# STM32F446RC_single_layer_V2_labelled.net
KiCad netlist of a schematic drawn in EAGLE
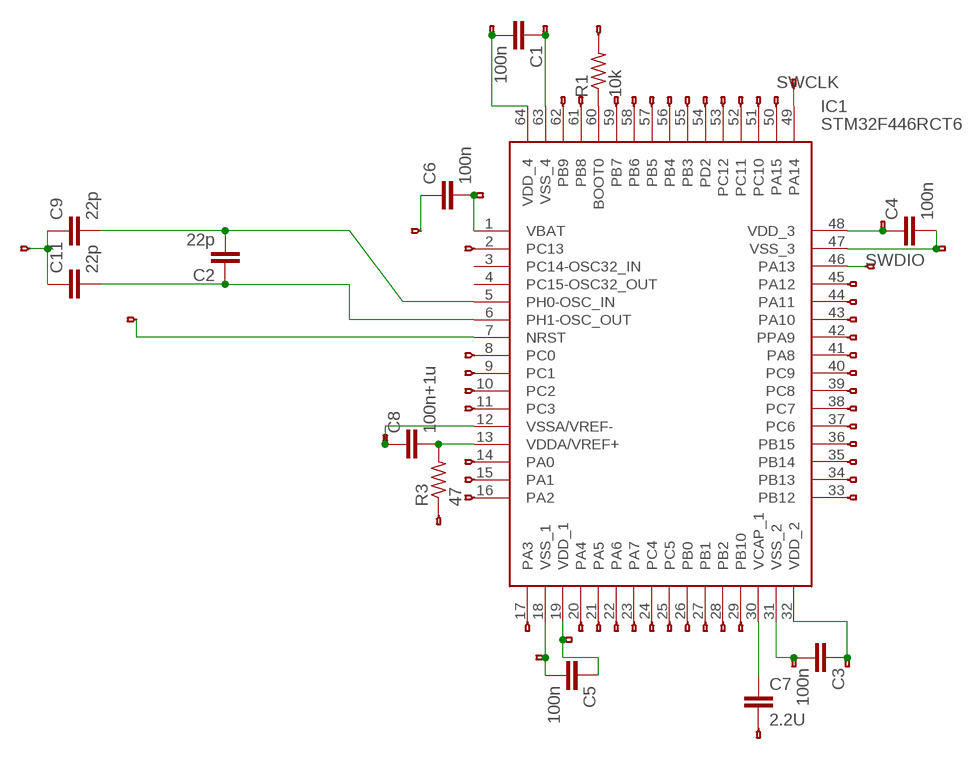
[diagram p0: schematic, sheet 1]

(export (version "E")
  (design (tool "Eeschema 10.0.6"))
  (components
    (comp (ref "C1")
      (value "100n")
      (footprint "eagle-import:C2.5-3")
      (libsource (lib "eagle-import") (part "C2,5-3"))
    )
    (comp (ref "C2")
      (value "22p")
      (footprint "eagle-import:C2.5-3")
      (libsource (lib "eagle-import") (part "C2,5-3"))
    )
    (comp (ref "C3")
      (value "100n")
      (footprint "eagle-import:C2.5-3")
      (libsource (lib "eagle-import") (part "C2,5-3"))
    )
    (comp (ref "C4")
      (value "100n")
      (footprint "eagle-import:C2.5-3")
      (libsource (lib "eagle-import") (part "C2,5-3"))
    )
    (comp (ref "C5")
      (value "100n")
      (footprint "eagle-import:C2.5-3")
      (libsource (lib "eagle-import") (part "C2,5-3"))
    )
    (comp (ref "C6")
      (value "100n")
      (footprint "eagle-import:C2.5-3")
      (libsource (lib "eagle-import") (part "C2,5-3"))
    )
    (comp (ref "C7")
      (value "2.2U")
      (footprint "eagle-import:C2.5-3")
      (libsource (lib "eagle-import") (part "C2,5-3"))
    )
    (comp (ref "C8")
      (value "100n+1u")
      (footprint "eagle-import:C2.5-3")
      (libsource (lib "eagle-import") (part "C2,5-3"))
    )
    (comp (ref "C9")
      (value "22p")
      (footprint "eagle-import:C2.5-3")
      (libsource (lib "eagle-import") (part "C2,5-3"))
    )
    (comp (ref "C11")
      (value "22p")
      (footprint "eagle-import:C2.5-3")
      (libsource (lib "eagle-import") (part "C2,5-3"))
    )
    (comp (ref "IC1")
      (value "STM32F446RCT6")
      (footprint "eagle-import:QFP50P1200X1200X160-64N")
      (fields (field (name "MOUSER_PART_NUMBER") "511-STM32F446RCT6"))
      (libsource (lib "eagle-import") (part "STM32F446RCT6"))
    )
    (comp (ref "JP1")
      (value "HEADERHOLE-HEADERHOLE")
      (footprint "eagle-import:1X1-HEADER-HOLE")
      (libsource (lib "eagle-import") (part "HEADERHOLE-HEADERHOLE"))
    )
    (comp (ref "JP2")
      (value "HEADERHOLE-HEADERHOLE")
      (footprint "eagle-import:1X1-HEADER-HOLE")
      (libsource (lib "eagle-import") (part "HEADERHOLE-HEADERHOLE"))
    )
    (comp (ref "JP3")
      (value "HEADERHOLE-HEADERHOLE")
      (footprint "eagle-import:1X1-HEADER-HOLE")
      (libsource (lib "eagle-import") (part "HEADERHOLE-HEADERHOLE"))
    )
    (comp (ref "JP4")
      (value "HEADERHOLE-HEADERHOLE")
      (footprint "eagle-import:1X1-HEADER-HOLE")
      (libsource (lib "eagle-import") (part "HEADERHOLE-HEADERHOLE"))
    )
    (comp (ref "JP5")
      (value "HEADERHOLE-HEADERHOLE")
      (footprint "eagle-import:1X1-HEADER-HOLE")
      (libsource (lib "eagle-import") (part "HEADERHOLE-HEADERHOLE"))
    )
    (comp (ref "JP6")
      (value "HEADERHOLE-HEADERHOLE")
      (footprint "eagle-import:1X1-HEADER-HOLE")
      (libsource (lib "eagle-import") (part "HEADERHOLE-HEADERHOLE"))
    )
    (comp (ref "JP7")
      (value "HEADERHOLE-HEADERHOLE")
      (footprint "eagle-import:1X1-HEADER-HOLE")
      (libsource (lib "eagle-import") (part "HEADERHOLE-HEADERHOLE"))
    )
    (comp (ref "JP9")
      (value "HEADERHOLE-HEADERHOLE")
      (footprint "eagle-import:1X1-HEADER-HOLE")
      (libsource (lib "eagle-import") (part "HEADERHOLE-HEADERHOLE"))
    )
    (comp (ref "JP10")
      (value "HEADERHOLE-HEADERHOLE")
      (footprint "eagle-import:1X1-HEADER-HOLE")
      (libsource (lib "eagle-import") (part "HEADERHOLE-HEADERHOLE"))
    )
    (comp (ref "JP11")
      (value "HEADERHOLE-HEADERHOLE")
      (footprint "eagle-import:1X1-HEADER-HOLE")
      (libsource (lib "eagle-import") (part "HEADERHOLE-HEADERHOLE"))
    )
    (comp (ref "JP12")
      (value "HEADERHOLE-HEADERHOLE")
      (footprint "eagle-import:1X1-HEADER-HOLE")
      (libsource (lib "eagle-import") (part "HEADERHOLE-HEADERHOLE"))
    )
    (comp (ref "JP13")
      (value "HEADERHOLE-HEADERHOLE")
      (footprint "eagle-import:1X1-HEADER-HOLE")
      (libsource (lib "eagle-import") (part "HEADERHOLE-HEADERHOLE"))
    )
    (comp (ref "JP14")
      (value "HEADERHOLE-HEADERHOLE")
      (footprint "eagle-import:1X1-HEADER-HOLE")
      (libsource (lib "eagle-import") (part "HEADERHOLE-HEADERHOLE"))
    )
    (comp (ref "JP15")
      (value "HEADERHOLE-HEADERHOLE")
      (footprint "eagle-import:1X1-HEADER-HOLE")
      (libsource (lib "eagle-import") (part "HEADERHOLE-HEADERHOLE"))
    )
    (comp (ref "JP16")
      (value "HEADERHOLE-HEADERHOLE")
      (footprint "eagle-import:1X1-HEADER-HOLE")
      (libsource (lib "eagle-import") (part "HEADERHOLE-HEADERHOLE"))
    )
    (comp (ref "JP17")
      (value "HEADERHOLE-HEADERHOLE")
      (footprint "eagle-import:1X1-HEADER-HOLE")
      (libsource (lib "eagle-import") (part "HEADERHOLE-HEADERHOLE"))
    )
    (comp (ref "JP18")
      (value "HEADERHOLE-HEADERHOLE")
      (footprint "eagle-import:1X1-HEADER-HOLE")
      (libsource (lib "eagle-import") (part "HEADERHOLE-HEADERHOLE"))
    )
    (comp (ref "JP19")
      (value "HEADERHOLE-HEADERHOLE")
      (footprint "eagle-import:1X1-HEADER-HOLE")
      (libsource (lib "eagle-import") (part "HEADERHOLE-HEADERHOLE"))
    )
    (comp (ref "JP20")
      (value "HEADERHOLE-HEADERHOLE")
      (footprint "eagle-import:1X1-HEADER-HOLE")
      (libsource (lib "eagle-import") (part "HEADERHOLE-HEADERHOLE"))
    )
    (comp (ref "JP21")
      (value "HEADERHOLE-HEADERHOLE")
      (footprint "eagle-import:1X1-HEADER-HOLE")
      (libsource (lib "eagle-import") (part "HEADERHOLE-HEADERHOLE"))
    )
    (comp (ref "JP22")
      (value "HEADERHOLE-HEADERHOLE")
      (footprint "eagle-import:1X1-HEADER-HOLE")
      (libsource (lib "eagle-import") (part "HEADERHOLE-HEADERHOLE"))
    )
    (comp (ref "JP23")
      (value "HEADERHOLE-HEADERHOLE")
      (footprint "eagle-import:1X1-HEADER-HOLE")
      (libsource (lib "eagle-import") (part "HEADERHOLE-HEADERHOLE"))
    )
    (comp (ref "JP24")
      (value "HEADERHOLE-HEADERHOLE")
      (footprint "eagle-import:1X1-HEADER-HOLE")
      (libsource (lib "eagle-import") (part "HEADERHOLE-HEADERHOLE"))
    )
    (comp (ref "JP25")
      (value "HEADERHOLE-HEADERHOLE")
      (footprint "eagle-import:1X1-HEADER-HOLE")
      (libsource (lib "eagle-import") (part "HEADERHOLE-HEADERHOLE"))
    )
    (comp (ref "JP26")
      (value "HEADERHOLE-HEADERHOLE")
      (footprint "eagle-import:1X1-HEADER-HOLE")
      (libsource (lib "eagle-import") (part "HEADERHOLE-HEADERHOLE"))
    )
    (comp (ref "JP27")
      (value "HEADERHOLE-HEADERHOLE")
      (footprint "eagle-import:1X1-HEADER-HOLE")
      (libsource (lib "eagle-import") (part "HEADERHOLE-HEADERHOLE"))
    )
    (comp (ref "JP28")
      (value "HEADERHOLE-HEADERHOLE")
      (footprint "eagle-import:1X1-HEADER-HOLE")
      (libsource (lib "eagle-import") (part "HEADERHOLE-HEADERHOLE"))
    )
    (comp (ref "JP29")
      (value "HEADERHOLE-HEADERHOLE")
      (footprint "eagle-import:1X1-HEADER-HOLE")
      (libsource (lib "eagle-import") (part "HEADERHOLE-HEADERHOLE"))
    )
    (comp (ref "JP30")
      (value "HEADERHOLE-HEADERHOLE")
      (footprint "eagle-import:1X1-HEADER-HOLE")
      (libsource (lib "eagle-import") (part "HEADERHOLE-HEADERHOLE"))
    )
    (comp (ref "JP31")
      (value "HEADERHOLE-HEADERHOLE")
      (footprint "eagle-import:1X1-HEADER-HOLE")
      (libsource (lib "eagle-import") (part "HEADERHOLE-HEADERHOLE"))
    )
    (comp (ref "JP32")
      (value "HEADERHOLE-HEADERHOLE")
      (footprint "eagle-import:1X1-HEADER-HOLE")
      (libsource (lib "eagle-import") (part "HEADERHOLE-HEADERHOLE"))
    )
    (comp (ref "JP33")
      (value "HEADERHOLE-HEADERHOLE")
      (footprint "eagle-import:1X1-HEADER-HOLE")
      (libsource (lib "eagle-import") (part "HEADERHOLE-HEADERHOLE"))
    )
    (comp (ref "JP34")
      (value "HEADERHOLE-HEADERHOLE")
      (footprint "eagle-import:1X1-HEADER-HOLE")
      (libsource (lib "eagle-import") (part "HEADERHOLE-HEADERHOLE"))
    )
    (comp (ref "JP35")
      (value "HEADERHOLE-HEADERHOLE")
      (footprint "eagle-import:1X1-HEADER-HOLE")
      (libsource (lib "eagle-import") (part "HEADERHOLE-HEADERHOLE"))
    )
    (comp (ref "JP36")
      (value "HEADERHOLE-HEADERHOLE")
      (footprint "eagle-import:1X1-HEADER-HOLE")
      (libsource (lib "eagle-import") (part "HEADERHOLE-HEADERHOLE"))
    )
    (comp (ref "JP37")
      (value "HEADERHOLE-HEADERHOLE")
      (footprint "eagle-import:1X1-HEADER-HOLE")
      (libsource (lib "eagle-import") (part "HEADERHOLE-HEADERHOLE"))
    )
    (comp (ref "JP38")
      (value "HEADERHOLE-HEADERHOLE")
      (footprint "eagle-import:1X1-HEADER-HOLE")
      (libsource (lib "eagle-import") (part "HEADERHOLE-HEADERHOLE"))
    )
    (comp (ref "JP39")
      (value "HEADERHOLE-HEADERHOLE")
      (footprint "eagle-import:1X1-HEADER-HOLE")
      (libsource (lib "eagle-import") (part "HEADERHOLE-HEADERHOLE"))
    )
    (comp (ref "JP40")
      (value "HEADERHOLE-HEADERHOLE")
      (footprint "eagle-import:1X1-HEADER-HOLE")
      (libsource (lib "eagle-import") (part "HEADERHOLE-HEADERHOLE"))
    )
    (comp (ref "JP41")
      (value "HEADERHOLE-HEADERHOLE")
      (footprint "eagle-import:1X1-HEADER-HOLE")
      (libsource (lib "eagle-import") (part "HEADERHOLE-HEADERHOLE"))
    )
    (comp (ref "JP42")
      (value "HEADERHOLE-HEADERHOLE")
      (footprint "eagle-import:1X1-HEADER-HOLE")
      (libsource (lib "eagle-import") (part "HEADERHOLE-HEADERHOLE"))
    )
    (comp (ref "JP43")
      (value "HEADERHOLE-HEADERHOLE")
      (footprint "eagle-import:1X1-HEADER-HOLE")
      (libsource (lib "eagle-import") (part "HEADERHOLE-HEADERHOLE"))
    )
    (comp (ref "JP44")
      (value "HEADERHOLE-HEADERHOLE")
      (footprint "eagle-import:1X1-HEADER-HOLE")
      (libsource (lib "eagle-import") (part "HEADERHOLE-HEADERHOLE"))
    )
    (comp (ref "JP45")
      (value "HEADERHOLE-HEADERHOLE")
      (footprint "eagle-import:1X1-HEADER-HOLE")
      (libsource (lib "eagle-import") (part "HEADERHOLE-HEADERHOLE"))
    )
    (comp (ref "JP46")
      (value "HEADERHOLE-HEADERHOLE")
      (footprint "eagle-import:1X1-HEADER-HOLE")
      (libsource (lib "eagle-import") (part "HEADERHOLE-HEADERHOLE"))
    )
    (comp (ref "JP47")
      (value "HEADERHOLE-HEADERHOLE")
      (footprint "eagle-import:1X1-HEADER-HOLE")
      (libsource (lib "eagle-import") (part "HEADERHOLE-HEADERHOLE"))
    )
    (comp (ref "JP48")
      (value "HEADERHOLE-HEADERHOLE")
      (footprint "eagle-import:1X1-HEADER-HOLE")
      (libsource (lib "eagle-import") (part "HEADERHOLE-HEADERHOLE"))
    )
    (comp (ref "JP49")
      (value "HEADERHOLE-HEADERHOLE")
      (footprint "eagle-import:1X1-HEADER-HOLE")
      (libsource (lib "eagle-import") (part "HEADERHOLE-HEADERHOLE"))
    )
    (comp (ref "JP50")
      (value "HEADERHOLE-HEADERHOLE")
      (footprint "eagle-import:1X1-HEADER-HOLE")
      (libsource (lib "eagle-import") (part "HEADERHOLE-HEADERHOLE"))
    )
    (comp (ref "JP51")
      (value "HEADERHOLE-HEADERHOLE")
      (footprint "eagle-import:1X1-HEADER-HOLE")
      (libsource (lib "eagle-import") (part "HEADERHOLE-HEADERHOLE"))
    )
    (comp (ref "JP52")
      (value "HEADERHOLE-HEADERHOLE")
      (footprint "eagle-import:1X1-HEADER-HOLE")
      (libsource (lib "eagle-import") (part "HEADERHOLE-HEADERHOLE"))
    )
    (comp (ref "JP53")
      (value "HEADERHOLE-HEADERHOLE")
      (footprint "eagle-import:1X1-HEADER-HOLE")
      (libsource (lib "eagle-import") (part "HEADERHOLE-HEADERHOLE"))
    )
    (comp (ref "JP54")
      (value "HEADERHOLE-HEADERHOLE")
      (footprint "eagle-import:1X1-HEADER-HOLE")
      (libsource (lib "eagle-import") (part "HEADERHOLE-HEADERHOLE"))
    )
    (comp (ref "JP55")
      (value "HEADERHOLE-HEADERHOLE")
      (footprint "eagle-import:1X1-HEADER-HOLE")
      (libsource (lib "eagle-import") (part "HEADERHOLE-HEADERHOLE"))
    )
    (comp (ref "JP56")
      (value "HEADERHOLE-HEADERHOLE")
      (footprint "eagle-import:1X1-HEADER-HOLE")
      (libsource (lib "eagle-import") (part "HEADERHOLE-HEADERHOLE"))
    )
    (comp (ref "JP57")
      (value "HEADERHOLE-HEADERHOLE")
      (footprint "eagle-import:1X1-HEADER-HOLE")
      (libsource (lib "eagle-import") (part "HEADERHOLE-HEADERHOLE"))
    )
    (comp (ref "JP58")
      (value "HEADERHOLE-HEADERHOLE")
      (footprint "eagle-import:1X1-HEADER-HOLE")
      (libsource (lib "eagle-import") (part "HEADERHOLE-HEADERHOLE"))
    )
    (comp (ref "JP59")
      (value "HEADERHOLE-HEADERHOLE")
      (footprint "eagle-import:1X1-HEADER-HOLE")
      (libsource (lib "eagle-import") (part "HEADERHOLE-HEADERHOLE"))
    )
    (comp (ref "JP61")
      (value "HEADERHOLE-HEADERHOLE")
      (footprint "eagle-import:1X1-HEADER-HOLE")
      (libsource (lib "eagle-import") (part "HEADERHOLE-HEADERHOLE"))
    )
    (comp (ref "JP62")
      (value "HEADERHOLE-HEADERHOLE")
      (footprint "eagle-import:1X1-HEADER-HOLE")
      (libsource (lib "eagle-import") (part "HEADERHOLE-HEADERHOLE"))
    )
    (comp (ref "JP63")
      (value "HEADERHOLE-HEADERHOLE")
      (footprint "eagle-import:1X1-HEADER-HOLE")
      (libsource (lib "eagle-import") (part "HEADERHOLE-HEADERHOLE"))
    )
    (comp (ref "JP65")
      (value "HEADERHOLE-HEADERHOLE")
      (footprint "eagle-import:1X1-HEADER-HOLE")
      (libsource (lib "eagle-import") (part "HEADERHOLE-HEADERHOLE"))
    )
    (comp (ref "R1")
      (value "10k")
      (footprint "eagle-import:0204V")
      (libsource (lib "eagle-import") (part "R-US_0204/2V"))
    )
    (comp (ref "R3")
      (value "47")
      (footprint "eagle-import:0204V")
      (libsource (lib "eagle-import") (part "R-US_0204/2V"))
    )
  )
  (nets
    (net (code "1") (name "/SWCLK") (class "Default")
      (node (ref "IC1") (pin "49") (pinfunction "PA14_49") (pintype "bidirectional"))
      (node (ref "JP55") (pin "1") (pinfunction "P$1_1") (pintype "bidirectional"))
    )
    (net (code "2") (name "/SWDIO") (class "Default")
      (node (ref "IC1") (pin "46") (pinfunction "PA13_46") (pintype "bidirectional"))
      (node (ref "JP54") (pin "1") (pinfunction "P$1_1") (pintype "bidirectional"))
    )
    (net (code "3") (name "Net-(IC1-BOOT0)") (class "Default")
      (node (ref "IC1") (pin "60") (pinfunction "BOOT0_60") (pintype "bidirectional"))
      (node (ref "R1") (pin "1") (pinfunction "1_1") (pintype "passive"))
    )
    (net (code "4") (name "Net-(IC1-NRST)") (class "Default")
      (node (ref "IC1") (pin "7") (pinfunction "NRST_7") (pintype "bidirectional"))
      (node (ref "JP63") (pin "1") (pinfunction "P$1_1") (pintype "bidirectional"))
    )
    (net (code "5") (name "Net-(IC1-PA0)") (class "Default")
      (node (ref "IC1") (pin "14") (pinfunction "PA0_14") (pintype "bidirectional"))
      (node (ref "JP34") (pin "1") (pinfunction "P$1_1") (pintype "bidirectional"))
    )
    (net (code "6") (name "Net-(IC1-PA1)") (class "Default")
      (node (ref "IC1") (pin "15") (pinfunction "PA1_15") (pintype "bidirectional"))
      (node (ref "JP35") (pin "1") (pinfunction "P$1_1") (pintype "bidirectional"))
    )
    (net (code "7") (name "Net-(IC1-PA2)") (class "Default")
      (node (ref "IC1") (pin "16") (pinfunction "PA2_16") (pintype "bidirectional"))
      (node (ref "JP36") (pin "1") (pinfunction "P$1_1") (pintype "bidirectional"))
    )
    (net (code "8") (name "Net-(IC1-PA3)") (class "Default")
      (node (ref "IC1") (pin "17") (pinfunction "PA3_17") (pintype "bidirectional"))
      (node (ref "JP24") (pin "1") (pinfunction "P$1_1") (pintype "bidirectional"))
    )
    (net (code "9") (name "Net-(IC1-PA4)") (class "Default")
      (node (ref "IC1") (pin "20") (pinfunction "PA4_20") (pintype "bidirectional"))
      (node (ref "JP21") (pin "1") (pinfunction "P$1_1") (pintype "bidirectional"))
    )
    (net (code "10") (name "Net-(IC1-PA5)") (class "Default")
      (node (ref "IC1") (pin "21") (pinfunction "PA5_21") (pintype "bidirectional"))
      (node (ref "JP19") (pin "1") (pinfunction "P$1_1") (pintype "bidirectional"))
    )
    (net (code "11") (name "Net-(IC1-PA6)") (class "Default")
      (node (ref "IC1") (pin "22") (pinfunction "PA6_22") (pintype "bidirectional"))
      (node (ref "JP9") (pin "1") (pinfunction "P$1_1") (pintype "bidirectional"))
    )
    (net (code "12") (name "Net-(IC1-PA7)") (class "Default")
      (node (ref "IC1") (pin "23") (pinfunction "PA7_23") (pintype "bidirectional"))
      (node (ref "JP11") (pin "1") (pinfunction "P$1_1") (pintype "bidirectional"))
    )
    (net (code "13") (name "Net-(IC1-PA8)") (class "Default")
      (node (ref "IC1") (pin "41") (pinfunction "PA8_41") (pintype "bidirectional"))
      (node (ref "JP28") (pin "1") (pinfunction "P$1_1") (pintype "bidirectional"))
    )
    (net (code "14") (name "Net-(IC1-PA10)") (class "Default")
      (node (ref "IC1") (pin "43") (pinfunction "PA10_43") (pintype "bidirectional"))
      (node (ref "JP33") (pin "1") (pinfunction "P$1_1") (pintype "bidirectional"))
    )
    (net (code "15") (name "Net-(IC1-PA11)") (class "Default")
      (node (ref "IC1") (pin "44") (pinfunction "PA11_44") (pintype "bidirectional"))
      (node (ref "JP32") (pin "1") (pinfunction "P$1_1") (pintype "bidirectional"))
    )
    (net (code "16") (name "Net-(IC1-PA12)") (class "Default")
      (node (ref "IC1") (pin "45") (pinfunction "PA12_45") (pintype "bidirectional"))
      (node (ref "JP25") (pin "1") (pinfunction "P$1_1") (pintype "bidirectional"))
    )
    (net (code "17") (name "Net-(IC1-PA15)") (class "Default")
      (node (ref "IC1") (pin "50") (pinfunction "PA15_50") (pintype "bidirectional"))
      (node (ref "JP45") (pin "1") (pinfunction "P$1_1") (pintype "bidirectional"))
    )
    (net (code "18") (name "Net-(IC1-PB0)") (class "Default")
      (node (ref "IC1") (pin "26") (pinfunction "PB0_26") (pintype "bidirectional"))
      (node (ref "JP22") (pin "1") (pinfunction "P$1_1") (pintype "bidirectional"))
    )
    (net (code "19") (name "Net-(IC1-PB1)") (class "Default")
      (node (ref "IC1") (pin "27") (pinfunction "PB1_27") (pintype "bidirectional"))
      (node (ref "JP17") (pin "1") (pinfunction "P$1_1") (pintype "bidirectional"))
    )
    (net (code "20") (name "Net-(IC1-PB2)") (class "Default")
      (node (ref "IC1") (pin "28") (pinfunction "PB2_28") (pintype "bidirectional"))
      (node (ref "JP16") (pin "1") (pinfunction "P$1_1") (pintype "bidirectional"))
    )
    (net (code "21") (name "Net-(IC1-PB3)") (class "Default")
      (node (ref "IC1") (pin "55") (pinfunction "PB3_55") (pintype "bidirectional"))
      (node (ref "JP44") (pin "1") (pinfunction "P$1_1") (pintype "bidirectional"))
    )
    (net (code "22") (name "Net-(IC1-PB4)") (class "Default")
      (node (ref "IC1") (pin "56") (pinfunction "PB4_56") (pintype "bidirectional"))
      (node (ref "JP40") (pin "1") (pinfunction "P$1_1") (pintype "bidirectional"))
    )
    (net (code "23") (name "Net-(IC1-PB5)") (class "Default")
      (node (ref "IC1") (pin "57") (pinfunction "PB5_57") (pintype "bidirectional"))
      (node (ref "JP41") (pin "1") (pinfunction "P$1_1") (pintype "bidirectional"))
    )
    (net (code "24") (name "Net-(IC1-PB6)") (class "Default")
      (node (ref "IC1") (pin "58") (pinfunction "PB6_58") (pintype "bidirectional"))
      (node (ref "JP42") (pin "1") (pinfunction "P$1_1") (pintype "bidirectional"))
    )
    (net (code "25") (name "Net-(IC1-PB7)") (class "Default")
      (node (ref "IC1") (pin "59") (pinfunction "PB7_59") (pintype "bidirectional"))
      (node (ref "JP43") (pin "1") (pinfunction "P$1_1") (pintype "bidirectional"))
    )
    (net (code "26") (name "Net-(IC1-PB8)") (class "Default")
      (node (ref "IC1") (pin "61") (pinfunction "PB8_61") (pintype "bidirectional"))
      (node (ref "JP46") (pin "1") (pinfunction "P$1_1") (pintype "bidirectional"))
    )
    (net (code "27") (name "Net-(IC1-PB9)") (class "Default")
      (node (ref "IC1") (pin "62") (pinfunction "PB9_62") (pintype "bidirectional"))
      (node (ref "JP47") (pin "1") (pinfunction "P$1_1") (pintype "bidirectional"))
    )
    (net (code "28") (name "Net-(IC1-PB10)") (class "Default")
      (node (ref "IC1") (pin "29") (pinfunction "PB10_29") (pintype "bidirectional"))
      (node (ref "JP14") (pin "1") (pinfunction "P$1_1") (pintype "bidirectional"))
    )
    (net (code "29") (name "Net-(IC1-PB12)") (class "Default")
      (node (ref "IC1") (pin "33") (pinfunction "PB12_33") (pintype "bidirectional"))
      (node (ref "JP18") (pin "1") (pinfunction "P$1_1") (pintype "bidirectional"))
    )
    (net (code "30") (name "Net-(IC1-PB13)") (class "Default")
      (node (ref "IC1") (pin "34") (pinfunction "PB13_34") (pintype "bidirectional"))
      (node (ref "JP13") (pin "1") (pinfunction "P$1_1") (pintype "bidirectional"))
    )
    (net (code "31") (name "Net-(IC1-PB14)") (class "Default")
      (node (ref "IC1") (pin "35") (pinfunction "PB14_35") (pintype "bidirectional"))
      (node (ref "JP6") (pin "1") (pinfunction "P$1_1") (pintype "bidirectional"))
    )
    (net (code "32") (name "Net-(IC1-PB15)") (class "Default")
      (node (ref "IC1") (pin "36") (pinfunction "PB15_36") (pintype "bidirectional"))
      (node (ref "JP10") (pin "1") (pinfunction "P$1_1") (pintype "bidirectional"))
    )
    (net (code "33") (name "Net-(IC1-PC0)") (class "Default")
      (node (ref "IC1") (pin "8") (pinfunction "PC0_8") (pintype "bidirectional"))
      (node (ref "JP29") (pin "1") (pinfunction "P$1_1") (pintype "bidirectional"))
    )
    (net (code "34") (name "Net-(IC1-PC1)") (class "Default")
      (node (ref "IC1") (pin "9") (pinfunction "PC1_9") (pintype "bidirectional"))
      (node (ref "JP27") (pin "1") (pinfunction "P$1_1") (pintype "bidirectional"))
    )
    (net (code "35") (name "Net-(IC1-PC2)") (class "Default")
      (node (ref "IC1") (pin "10") (pinfunction "PC2_10") (pintype "bidirectional"))
      (node (ref "JP3") (pin "1") (pinfunction "P$1_1") (pintype "bidirectional"))
    )
    (net (code "36") (name "Net-(IC1-PC3)") (class "Default")
      (node (ref "IC1") (pin "11") (pinfunction "PC3_11") (pintype "bidirectional"))
      (node (ref "JP4") (pin "1") (pinfunction "P$1_1") (pintype "bidirectional"))
    )
    (net (code "37") (name "Net-(IC1-PC4)") (class "Default")
      (node (ref "IC1") (pin "24") (pinfunction "PC4_24") (pintype "bidirectional"))
      (node (ref "JP12") (pin "1") (pinfunction "P$1_1") (pintype "bidirectional"))
    )
    (net (code "38") (name "Net-(IC1-PC5)") (class "Default")
      (node (ref "IC1") (pin "25") (pinfunction "PC5_25") (pintype "bidirectional"))
      (node (ref "JP23") (pin "1") (pinfunction "P$1_1") (pintype "bidirectional"))
    )
    (net (code "39") (name "Net-(IC1-PC6)") (class "Default")
      (node (ref "IC1") (pin "37") (pinfunction "PC6_37") (pintype "bidirectional"))
      (node (ref "JP1") (pin "1") (pinfunction "P$1_1") (pintype "bidirectional"))
    )
    (net (code "40") (name "Net-(IC1-PC7)") (class "Default")
      (node (ref "IC1") (pin "38") (pinfunction "PC7_38") (pintype "bidirectional"))
      (node (ref "JP15") (pin "1") (pinfunction "P$1_1") (pintype "bidirectional"))
    )
    (net (code "41") (name "Net-(IC1-PC8)") (class "Default")
      (node (ref "IC1") (pin "39") (pinfunction "PC8_39") (pintype "bidirectional"))
      (node (ref "JP2") (pin "1") (pinfunction "P$1_1") (pintype "bidirectional"))
    )
    (net (code "42") (name "Net-(IC1-PC9)") (class "Default")
      (node (ref "IC1") (pin "40") (pinfunction "PC9_40") (pintype "bidirectional"))
      (node (ref "JP30") (pin "1") (pinfunction "P$1_1") (pintype "bidirectional"))
    )
    (net (code "43") (name "Net-(IC1-PC10)") (class "Default")
      (node (ref "IC1") (pin "51") (pinfunction "PC10_51") (pintype "bidirectional"))
      (node (ref "JP37") (pin "1") (pinfunction "P$1_1") (pintype "bidirectional"))
    )
    (net (code "44") (name "Net-(IC1-PC11)") (class "Default")
      (node (ref "IC1") (pin "52") (pinfunction "PC11_52") (pintype "bidirectional"))
      (node (ref "JP5") (pin "1") (pinfunction "P$1_1") (pintype "bidirectional"))
    )
    (net (code "45") (name "Net-(IC1-PC12)") (class "Default")
      (node (ref "IC1") (pin "53") (pinfunction "PC12_53") (pintype "bidirectional"))
      (node (ref "JP39") (pin "1") (pinfunction "P$1_1") (pintype "bidirectional"))
    )
    (net (code "46") (name "Net-(IC1-PC13)") (class "Default")
      (node (ref "IC1") (pin "2") (pinfunction "PC13_2") (pintype "bidirectional"))
      (node (ref "JP26") (pin "1") (pinfunction "P$1_1") (pintype "bidirectional"))
    )
    (net (code "47") (name "Net-(IC1-PD2)") (class "Default")
      (node (ref "IC1") (pin "54") (pinfunction "PD2_54") (pintype "bidirectional"))
      (node (ref "JP38") (pin "1") (pinfunction "P$1_1") (pintype "bidirectional"))
    )
    (net (code "48") (name "Net-(IC1-PH0-OSC_IN)") (class "Default")
      (node (ref "C2") (pin "2") (pinfunction "2_2") (pintype "passive"))
      (node (ref "C9") (pin "2") (pinfunction "2_2") (pintype "passive"))
      (node (ref "IC1") (pin "5") (pinfunction "PH0-OSC_IN_5") (pintype "bidirectional"))
    )
    (net (code "49") (name "Net-(IC1-PH1-OSC_OUT)") (class "Default")
      (node (ref "C11") (pin "2") (pinfunction "2_2") (pintype "passive"))
      (node (ref "C2") (pin "1") (pinfunction "1_1") (pintype "passive"))
      (node (ref "IC1") (pin "6") (pinfunction "PH1-OSC_OUT_6") (pintype "bidirectional"))
    )
    (net (code "50") (name "Net-(IC1-PPA9)") (class "Default")
      (node (ref "IC1") (pin "42") (pinfunction "PPA9_42") (pintype "bidirectional"))
      (node (ref "JP31") (pin "1") (pinfunction "P$1_1") (pintype "bidirectional"))
    )
    (net (code "51") (name "Net-(IC1-VBAT)") (class "Default")
      (node (ref "C6") (pin "2") (pinfunction "2_2") (pintype "passive"))
      (node (ref "IC1") (pin "1") (pinfunction "VBAT_1") (pintype "bidirectional"))
      (node (ref "JP7") (pin "1") (pinfunction "P$1_1") (pintype "bidirectional"))
    )
    (net (code "52") (name "Net-(IC1-VCAP_1)") (class "Default")
      (node (ref "C7") (pin "1") (pinfunction "1_1") (pintype "passive"))
      (node (ref "IC1") (pin "30") (pinfunction "VCAP_1_30") (pintype "bidirectional"))
    )
    (net (code "53") (name "Net-(IC1-VDDA{slash}VREF+)") (class "Default")
      (node (ref "C8") (pin "2") (pinfunction "2_2") (pintype "passive"))
      (node (ref "IC1") (pin "13") (pinfunction "VDDA/VREF+_13") (pintype "bidirectional"))
      (node (ref "R3") (pin "2") (pinfunction "2_2") (pintype "passive"))
    )
    (net (code "54") (name "Net-(IC1-VDD_1)") (class "Default")
      (node (ref "C5") (pin "1") (pinfunction "1_1") (pintype "passive"))
      (node (ref "IC1") (pin "19") (pinfunction "VDD_1_19") (pintype "bidirectional"))
      (node (ref "JP48") (pin "1") (pinfunction "P$1_1") (pintype "bidirectional"))
    )
    (net (code "55") (name "Net-(IC1-VDD_2)") (class "Default")
      (node (ref "C3") (pin "1") (pinfunction "1_1") (pintype "passive"))
      (node (ref "IC1") (pin "32") (pinfunction "VDD_2_32") (pintype "bidirectional"))
      (node (ref "JP51") (pin "1") (pinfunction "P$1_1") (pintype "bidirectional"))
    )
    (net (code "56") (name "Net-(IC1-VDD_3)") (class "Default")
      (node (ref "C4") (pin "1") (pinfunction "1_1") (pintype "passive"))
      (node (ref "IC1") (pin "48") (pinfunction "VDD_3_48") (pintype "bidirectional"))
      (node (ref "JP53") (pin "1") (pinfunction "P$1_1") (pintype "bidirectional"))
    )
    (net (code "57") (name "Net-(IC1-VDD_4)") (class "Default")
      (node (ref "C1") (pin "2") (pinfunction "2_2") (pintype "passive"))
      (node (ref "IC1") (pin "64") (pinfunction "VDD_4_64") (pintype "bidirectional"))
      (node (ref "JP58") (pin "1") (pinfunction "P$1_1") (pintype "bidirectional"))
    )
    (net (code "58") (name "Net-(IC1-VSSA{slash}VREF-)") (class "Default")
      (node (ref "C8") (pin "1") (pinfunction "1_1") (pintype "passive"))
      (node (ref "IC1") (pin "12") (pinfunction "VSSA/VREF-_12") (pintype "bidirectional"))
      (node (ref "JP62") (pin "1") (pinfunction "P$1_1") (pintype "bidirectional"))
    )
    (net (code "59") (name "Net-(IC1-VSS_1)") (class "Default")
      (node (ref "C5") (pin "2") (pinfunction "2_2") (pintype "passive"))
      (node (ref "IC1") (pin "18") (pinfunction "VSS_1_18") (pintype "bidirectional"))
      (node (ref "JP20") (pin "1") (pinfunction "P$1_1") (pintype "bidirectional"))
    )
    (net (code "60") (name "Net-(IC1-VSS_2)") (class "Default")
      (node (ref "C3") (pin "2") (pinfunction "2_2") (pintype "passive"))
      (node (ref "IC1") (pin "31") (pinfunction "VSS_2_31") (pintype "bidirectional"))
      (node (ref "JP50") (pin "1") (pinfunction "P$1_1") (pintype "bidirectional"))
    )
    (net (code "61") (name "Net-(IC1-VSS_3)") (class "Default")
      (node (ref "C4") (pin "2") (pinfunction "2_2") (pintype "passive"))
      (node (ref "IC1") (pin "47") (pinfunction "VSS_3_47") (pintype "bidirectional"))
      (node (ref "JP52") (pin "1") (pinfunction "P$1_1") (pintype "bidirectional"))
    )
    (net (code "62") (name "Net-(IC1-VSS_4)") (class "Default")
      (node (ref "C1") (pin "1") (pinfunction "1_1") (pintype "passive"))
      (node (ref "IC1") (pin "63") (pinfunction "VSS_4_63") (pintype "bidirectional"))
      (node (ref "JP57") (pin "1") (pinfunction "P$1_1") (pintype "bidirectional"))
    )
    (net (code "63") (name "Net-(JP49-P$1)") (class "Default")
      (node (ref "C7") (pin "2") (pinfunction "2_2") (pintype "passive"))
      (node (ref "JP49") (pin "1") (pinfunction "P$1_1") (pintype "bidirectional"))
    )
    (net (code "64") (name "Net-(JP56-P$1)") (class "Default")
      (node (ref "JP56") (pin "1") (pinfunction "P$1_1") (pintype "bidirectional"))
      (node (ref "R1") (pin "2") (pinfunction "2_2") (pintype "passive"))
    )
    (net (code "65") (name "Net-(JP59-P$1)") (class "Default")
      (node (ref "C6") (pin "1") (pinfunction "1_1") (pintype "passive"))
      (node (ref "JP59") (pin "1") (pinfunction "P$1_1") (pintype "bidirectional"))
    )
    (net (code "66") (name "Net-(JP61-P$1)") (class "Default")
      (node (ref "JP61") (pin "1") (pinfunction "P$1_1") (pintype "bidirectional"))
      (node (ref "R3") (pin "1") (pinfunction "1_1") (pintype "passive"))
    )
    (net (code "67") (name "Net-(JP65-P$1)") (class "Default")
      (node (ref "C11") (pin "1") (pinfunction "1_1") (pintype "passive"))
      (node (ref "C9") (pin "1") (pinfunction "1_1") (pintype "passive"))
      (node (ref "JP65") (pin "1") (pinfunction "P$1_1") (pintype "bidirectional"))
    )
    (net (code "68") (name "unconnected-(IC1-PC14-OSC32_IN-Pad3)") (class "Default")
      (node (ref "IC1") (pin "3") (pinfunction "PC14-OSC32_IN_3") (pintype "bidirectional"))
    )
    (net (code "69") (name "unconnected-(IC1-PC15-OSC32_OUT-Pad4)") (class "Default")
      (node (ref "IC1") (pin "4") (pinfunction "PC15-OSC32_OUT_4") (pintype "bidirectional"))
    )
  )
)
